# FrontDoorController.net
KiCad netlist of a schematic drawn in EAGLE
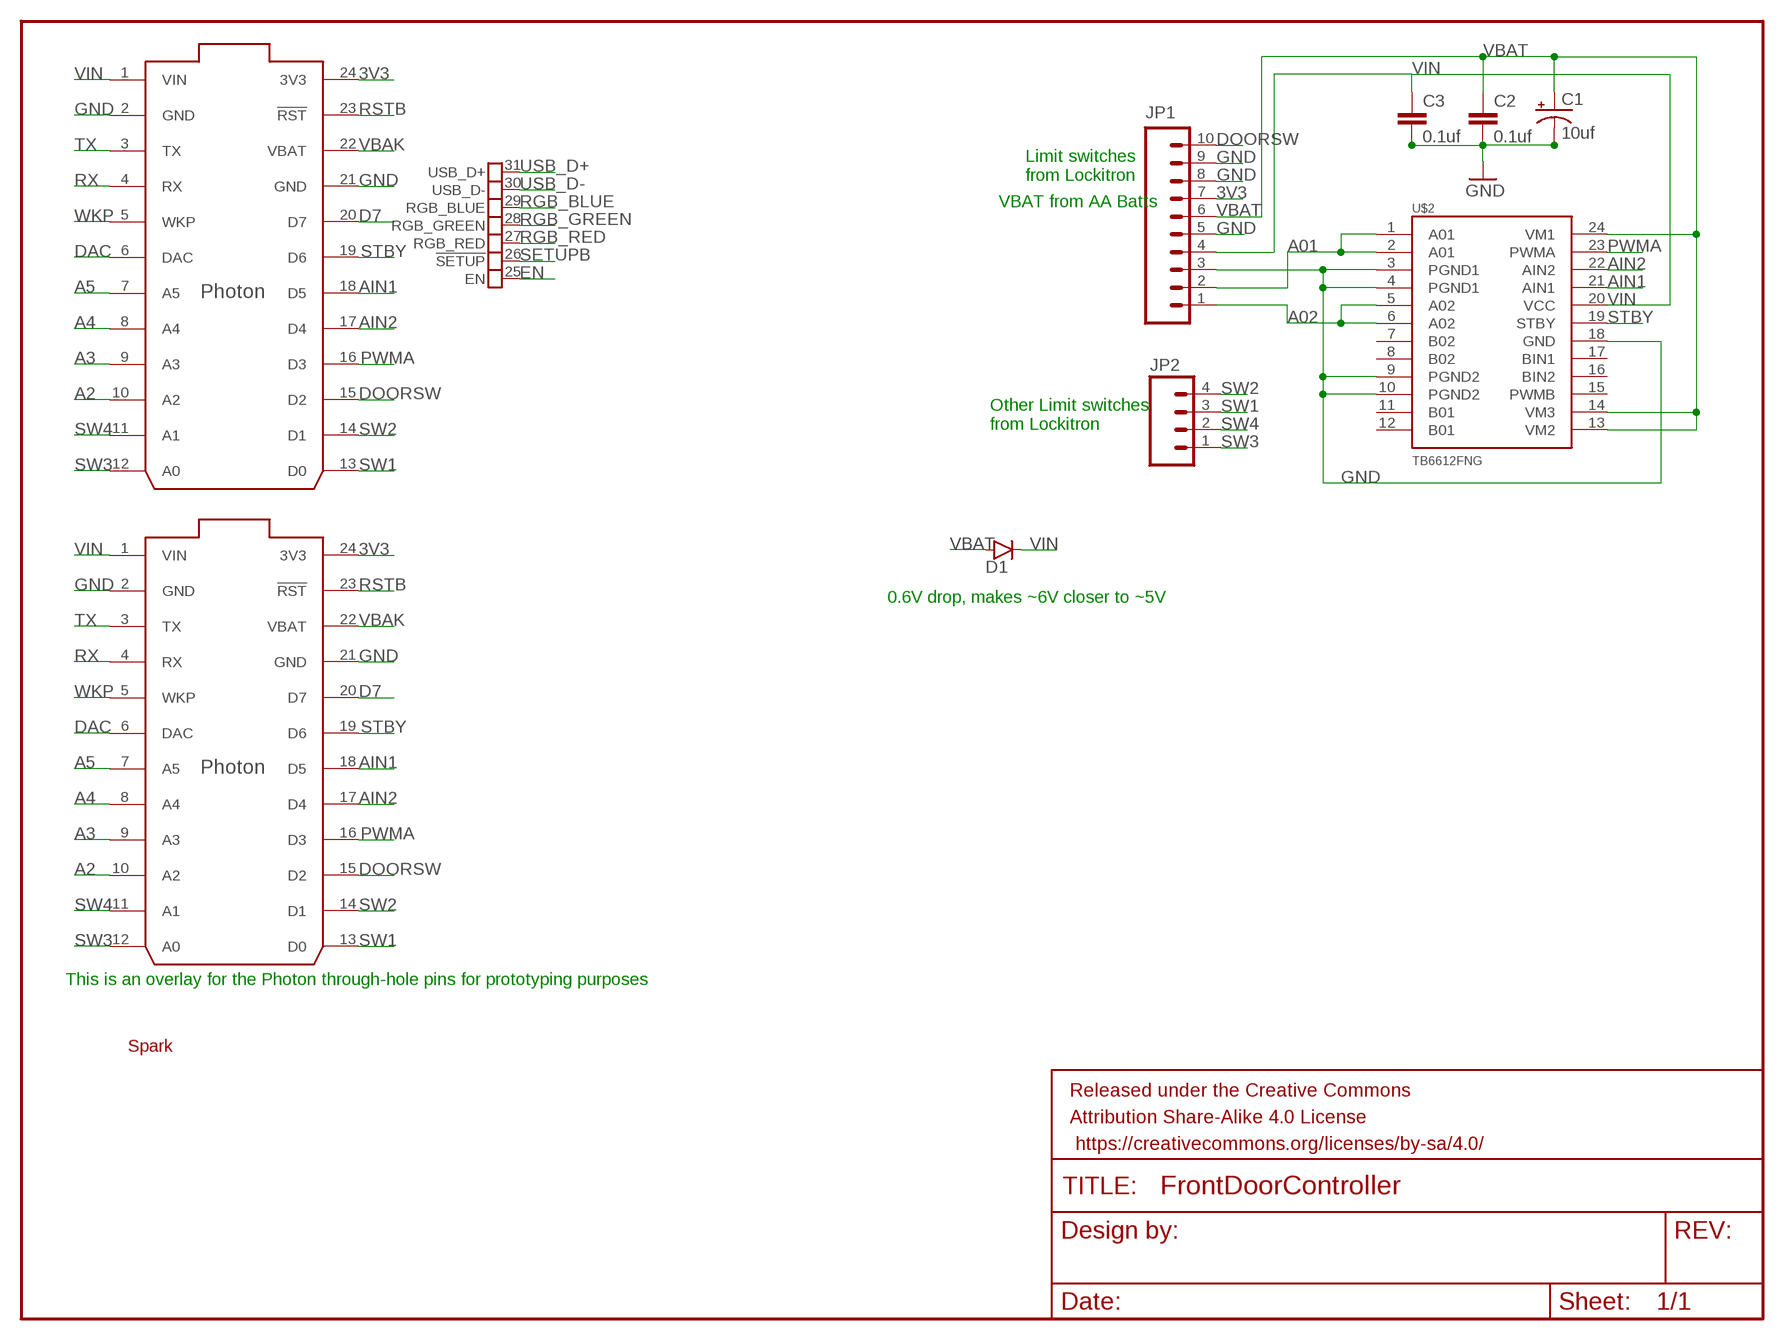
[diagram p0: schematic, sheet 1]

(export (version "E")
  (design (tool "Eeschema 10.0.6"))
  (components
    (comp (ref "C1")
      (value "10uf")
      (footprint "eagle-import:EIA3528")
      (libsource (lib "eagle-import") (part "CAP_POL3528"))
    )
    (comp (ref "C2")
      (value "0.1uf")
      (footprint "eagle-import:0402-CAP")
      (libsource (lib "eagle-import") (part "CAP0402-CAP"))
    )
    (comp (ref "C3")
      (value "0.1uf")
      (footprint "eagle-import:0402-CAP")
      (libsource (lib "eagle-import") (part "CAP0402-CAP"))
    )
    (comp (ref "D1")
      (value "DIODEPTH")
      (footprint "eagle-import:DIODE-1N4001")
      (libsource (lib "eagle-import") (part "DIODEPTH"))
    )
    (comp (ref "FRAME1")
      (value "FRAME-LETTER")
      (footprint "eagle-import:CREATIVE_COMMONS")
      (libsource (lib "eagle-import") (part "FRAME-LETTER"))
    )
    (comp (ref "JP1")
      (value "M10LOCK")
      (footprint "eagle-import:1X10_LOCK")
      (libsource (lib "eagle-import") (part "M10LOCK"))
    )
    (comp (ref "JP2")
      (value "M04LOCK")
      (footprint "eagle-import:1X04_LOCK")
      (libsource (lib "eagle-import") (part "M04LOCK"))
    )
    (comp (ref "PHOTON")
      (value "PHOTON_SMD")
      (footprint "eagle-import:PHOTON_SMD")
      (libsource (lib "eagle-import") (part "PHOTON_SMD"))
    )
    (comp (ref "U$1")
      (value "SPARK_LOGOLARGE")
      (footprint "eagle-import:SPARK_LOGO")
      (libsource (lib "eagle-import") (part "SPARK_LOGOLARGE"))
    )
    (comp (ref "U$2")
      (value "TB6612FNG")
      (footprint "eagle-import:SSOP24")
      (libsource (lib "eagle-import") (part "TB6612FNG"))
    )
    (comp (ref "U$3")
      (value "PHOTON_WITH_HEADERS")
      (footprint "eagle-import:PHOTON")
      (libsource (lib "eagle-import") (part "PHOTON_WITH_HEADERS"))
    )
  )
  (nets
    (net (code "1") (name "/3V3") (class "Default")
      (node (ref "JP1") (pin "7") (pinfunction "7_7") (pintype "passive"))
      (node (ref "PHOTON") (pin "24") (pinfunction "3V3_24") (pintype "power_in"))
      (node (ref "U$3") (pin "24") (pinfunction "3V3_24") (pintype "power_in"))
    )
    (net (code "2") (name "/A01") (class "Default")
      (node (ref "JP1") (pin "2") (pinfunction "2_2") (pintype "passive"))
      (node (ref "U$2") (pin "1") (pinfunction "A01_1") (pintype "bidirectional"))
      (node (ref "U$2") (pin "2") (pinfunction "A01_2") (pintype "bidirectional"))
    )
    (net (code "3") (name "/A2") (class "Default")
      (node (ref "PHOTON") (pin "10") (pinfunction "A2_10") (pintype "bidirectional"))
      (node (ref "U$3") (pin "10") (pinfunction "A2_10") (pintype "bidirectional"))
    )
    (net (code "4") (name "/A02") (class "Default")
      (node (ref "JP1") (pin "1") (pinfunction "1_1") (pintype "passive"))
      (node (ref "U$2") (pin "5") (pinfunction "A02_5") (pintype "bidirectional"))
      (node (ref "U$2") (pin "6") (pinfunction "A02_6") (pintype "bidirectional"))
    )
    (net (code "5") (name "/A3") (class "Default")
      (node (ref "PHOTON") (pin "9") (pinfunction "A3_9") (pintype "bidirectional"))
      (node (ref "U$3") (pin "9") (pinfunction "A3_9") (pintype "bidirectional"))
    )
    (net (code "6") (name "/A4") (class "Default")
      (node (ref "PHOTON") (pin "8") (pinfunction "A4_8") (pintype "bidirectional"))
      (node (ref "U$3") (pin "8") (pinfunction "A4_8") (pintype "bidirectional"))
    )
    (net (code "7") (name "/A5") (class "Default")
      (node (ref "PHOTON") (pin "7") (pinfunction "A5_7") (pintype "bidirectional"))
      (node (ref "U$3") (pin "7") (pinfunction "A5_7") (pintype "bidirectional"))
    )
    (net (code "8") (name "/AIN1") (class "Default")
      (node (ref "PHOTON") (pin "18") (pinfunction "D5_18") (pintype "bidirectional"))
      (node (ref "U$2") (pin "21") (pinfunction "AIN1_21") (pintype "bidirectional"))
      (node (ref "U$3") (pin "18") (pinfunction "D5_18") (pintype "bidirectional"))
    )
    (net (code "9") (name "/AIN2") (class "Default")
      (node (ref "PHOTON") (pin "17") (pinfunction "D4_17") (pintype "bidirectional"))
      (node (ref "U$2") (pin "22") (pinfunction "AIN2_22") (pintype "bidirectional"))
      (node (ref "U$3") (pin "17") (pinfunction "D4_17") (pintype "bidirectional"))
    )
    (net (code "10") (name "/D7") (class "Default")
      (node (ref "PHOTON") (pin "20") (pinfunction "D7_20") (pintype "bidirectional"))
      (node (ref "U$3") (pin "20") (pinfunction "D7_20") (pintype "bidirectional"))
    )
    (net (code "11") (name "/DAC") (class "Default")
      (node (ref "PHOTON") (pin "6") (pinfunction "DAC_6") (pintype "bidirectional"))
      (node (ref "U$3") (pin "6") (pinfunction "DAC_6") (pintype "bidirectional"))
    )
    (net (code "12") (name "/DOORSW") (class "Default")
      (node (ref "JP1") (pin "10") (pinfunction "10_10") (pintype "passive"))
      (node (ref "PHOTON") (pin "15") (pinfunction "D2_15") (pintype "bidirectional"))
      (node (ref "U$3") (pin "15") (pinfunction "D2_15") (pintype "bidirectional"))
    )
    (net (code "13") (name "/EN") (class "Default")
      (node (ref "PHOTON") (pin "25") (pinfunction "EN_25") (pintype "bidirectional"))
    )
    (net (code "14") (name "/PWMA") (class "Default")
      (node (ref "PHOTON") (pin "16") (pinfunction "D3_16") (pintype "bidirectional"))
      (node (ref "U$2") (pin "23") (pinfunction "PWMA_23") (pintype "bidirectional"))
      (node (ref "U$3") (pin "16") (pinfunction "D3_16") (pintype "bidirectional"))
    )
    (net (code "15") (name "/RGB_BLUE") (class "Default")
      (node (ref "PHOTON") (pin "29") (pinfunction "RGB_BLUE_29") (pintype "bidirectional"))
    )
    (net (code "16") (name "/RGB_GREEN") (class "Default")
      (node (ref "PHOTON") (pin "28") (pinfunction "RGB_GREEN_28") (pintype "bidirectional"))
    )
    (net (code "17") (name "/RGB_RED") (class "Default")
      (node (ref "PHOTON") (pin "27") (pinfunction "RGB_RED_27") (pintype "bidirectional"))
    )
    (net (code "18") (name "/RSTB") (class "Default")
      (node (ref "PHOTON") (pin "23") (pinfunction "~{RST}_23") (pintype "bidirectional"))
      (node (ref "U$3") (pin "23") (pinfunction "~{RST}_23") (pintype "bidirectional"))
    )
    (net (code "19") (name "/RX") (class "Default")
      (node (ref "PHOTON") (pin "4") (pinfunction "RX_4") (pintype "bidirectional"))
      (node (ref "U$3") (pin "4") (pinfunction "RX_4") (pintype "bidirectional"))
    )
    (net (code "20") (name "/SETUPB") (class "Default")
      (node (ref "PHOTON") (pin "26") (pinfunction "~{SETUP}_26") (pintype "bidirectional"))
    )
    (net (code "21") (name "/STBY") (class "Default")
      (node (ref "PHOTON") (pin "19") (pinfunction "D6_19") (pintype "bidirectional"))
      (node (ref "U$2") (pin "19") (pinfunction "STBY_19") (pintype "bidirectional"))
      (node (ref "U$3") (pin "19") (pinfunction "D6_19") (pintype "bidirectional"))
    )
    (net (code "22") (name "/SW1") (class "Default")
      (node (ref "JP2") (pin "3") (pinfunction "3_3") (pintype "passive"))
      (node (ref "PHOTON") (pin "13") (pinfunction "D0_13") (pintype "bidirectional"))
      (node (ref "U$3") (pin "13") (pinfunction "D0_13") (pintype "bidirectional"))
    )
    (net (code "23") (name "/SW2") (class "Default")
      (node (ref "JP2") (pin "4") (pinfunction "4_4") (pintype "passive"))
      (node (ref "PHOTON") (pin "14") (pinfunction "D1_14") (pintype "bidirectional"))
      (node (ref "U$3") (pin "14") (pinfunction "D1_14") (pintype "bidirectional"))
    )
    (net (code "24") (name "/SW3") (class "Default")
      (node (ref "JP2") (pin "1") (pinfunction "1_1") (pintype "passive"))
      (node (ref "PHOTON") (pin "12") (pinfunction "A0_12") (pintype "bidirectional"))
      (node (ref "U$3") (pin "12") (pinfunction "A0_12") (pintype "bidirectional"))
    )
    (net (code "25") (name "/SW4") (class "Default")
      (node (ref "JP2") (pin "2") (pinfunction "2_2") (pintype "passive"))
      (node (ref "PHOTON") (pin "11") (pinfunction "A1_11") (pintype "bidirectional"))
      (node (ref "U$3") (pin "11") (pinfunction "A1_11") (pintype "bidirectional"))
    )
    (net (code "26") (name "/TX") (class "Default")
      (node (ref "PHOTON") (pin "3") (pinfunction "TX_3") (pintype "bidirectional"))
      (node (ref "U$3") (pin "3") (pinfunction "TX_3") (pintype "bidirectional"))
    )
    (net (code "27") (name "/USB_D+") (class "Default")
      (node (ref "PHOTON") (pin "31") (pinfunction "USB_D+_31") (pintype "bidirectional"))
    )
    (net (code "28") (name "/USB_D-") (class "Default")
      (node (ref "PHOTON") (pin "30") (pinfunction "USB_D-_30") (pintype "bidirectional"))
    )
    (net (code "29") (name "/VBAK") (class "Default")
      (node (ref "PHOTON") (pin "22") (pinfunction "VBAT_22") (pintype "power_in"))
      (node (ref "U$3") (pin "22") (pinfunction "VBAT_22") (pintype "power_in"))
    )
    (net (code "30") (name "/VBAT") (class "Default")
      (node (ref "C1") (pin "A") (pinfunction "+_A") (pintype "passive"))
      (node (ref "C2") (pin "1") (pinfunction "1_1") (pintype "passive"))
      (node (ref "D1") (pin "A") (pinfunction "A_A") (pintype "passive"))
      (node (ref "JP1") (pin "6") (pinfunction "6_6") (pintype "passive"))
      (node (ref "U$2") (pin "13") (pinfunction "VM2_13") (pintype "bidirectional"))
      (node (ref "U$2") (pin "14") (pinfunction "VM3_14") (pintype "bidirectional"))
      (node (ref "U$2") (pin "24") (pinfunction "VM1_24") (pintype "bidirectional"))
    )
    (net (code "31") (name "/VIN") (class "Default")
      (node (ref "C3") (pin "1") (pinfunction "1_1") (pintype "passive"))
      (node (ref "D1") (pin "C") (pinfunction "C_C") (pintype "passive"))
      (node (ref "JP1") (pin "4") (pinfunction "4_4") (pintype "passive"))
      (node (ref "PHOTON") (pin "1") (pinfunction "VIN_1") (pintype "power_in"))
      (node (ref "U$2") (pin "20") (pinfunction "VCC_20") (pintype "bidirectional"))
      (node (ref "U$3") (pin "1") (pinfunction "VIN_1") (pintype "power_in"))
    )
    (net (code "32") (name "/WKP") (class "Default")
      (node (ref "PHOTON") (pin "5") (pinfunction "WKP_5") (pintype "bidirectional"))
      (node (ref "U$3") (pin "5") (pinfunction "WKP_5") (pintype "bidirectional"))
    )
    (net (code "33") (name "GND") (class "Default")
      (node (ref "C1") (pin "C") (pinfunction "-_C") (pintype "passive"))
      (node (ref "C2") (pin "2") (pinfunction "2_2") (pintype "passive"))
      (node (ref "C3") (pin "2") (pinfunction "2_2") (pintype "passive"))
      (node (ref "JP1") (pin "3") (pinfunction "3_3") (pintype "passive"))
      (node (ref "JP1") (pin "5") (pinfunction "5_5") (pintype "passive"))
      (node (ref "JP1") (pin "8") (pinfunction "8_8") (pintype "passive"))
      (node (ref "JP1") (pin "9") (pinfunction "9_9") (pintype "passive"))
      (node (ref "PHOTON") (pin "2") (pinfunction "GND_2") (pintype "power_in"))
      (node (ref "PHOTON") (pin "21") (pinfunction "GND_21") (pintype "power_in"))
      (node (ref "U$2") (pin "10") (pinfunction "PGND2_10") (pintype "bidirectional"))
      (node (ref "U$2") (pin "18") (pinfunction "GND_18") (pintype "bidirectional"))
      (node (ref "U$2") (pin "3") (pinfunction "PGND1_3") (pintype "bidirectional"))
      (node (ref "U$2") (pin "4") (pinfunction "PGND1_4") (pintype "bidirectional"))
      (node (ref "U$2") (pin "9") (pinfunction "PGND2_9") (pintype "bidirectional"))
      (node (ref "U$3") (pin "2") (pinfunction "GND_2") (pintype "power_in"))
      (node (ref "U$3") (pin "21") (pinfunction "GND_21") (pintype "power_in"))
    )
    (net (code "34") (name "unconnected-(U$2-B01-Pad11)") (class "Default")
      (node (ref "U$2") (pin "11") (pinfunction "B01_11") (pintype "bidirectional"))
    )
    (net (code "35") (name "unconnected-(U$2-B01-Pad12)") (class "Default")
      (node (ref "U$2") (pin "12") (pinfunction "B01_12") (pintype "bidirectional"))
    )
    (net (code "36") (name "unconnected-(U$2-B02-Pad7)") (class "Default")
      (node (ref "U$2") (pin "7") (pinfunction "B02_7") (pintype "bidirectional"))
    )
    (net (code "37") (name "unconnected-(U$2-B02-Pad8)") (class "Default")
      (node (ref "U$2") (pin "8") (pinfunction "B02_8") (pintype "bidirectional"))
    )
    (net (code "38") (name "unconnected-(U$2-BIN1-Pad17)") (class "Default")
      (node (ref "U$2") (pin "17") (pinfunction "BIN1_17") (pintype "bidirectional"))
    )
    (net (code "39") (name "unconnected-(U$2-BIN2-Pad16)") (class "Default")
      (node (ref "U$2") (pin "16") (pinfunction "BIN2_16") (pintype "bidirectional"))
    )
    (net (code "40") (name "unconnected-(U$2-PWMB-Pad15)") (class "Default")
      (node (ref "U$2") (pin "15") (pinfunction "PWMB_15") (pintype "bidirectional"))
    )
  )
)
